# main.net
KiCad netlist of a schematic drawn in EAGLE
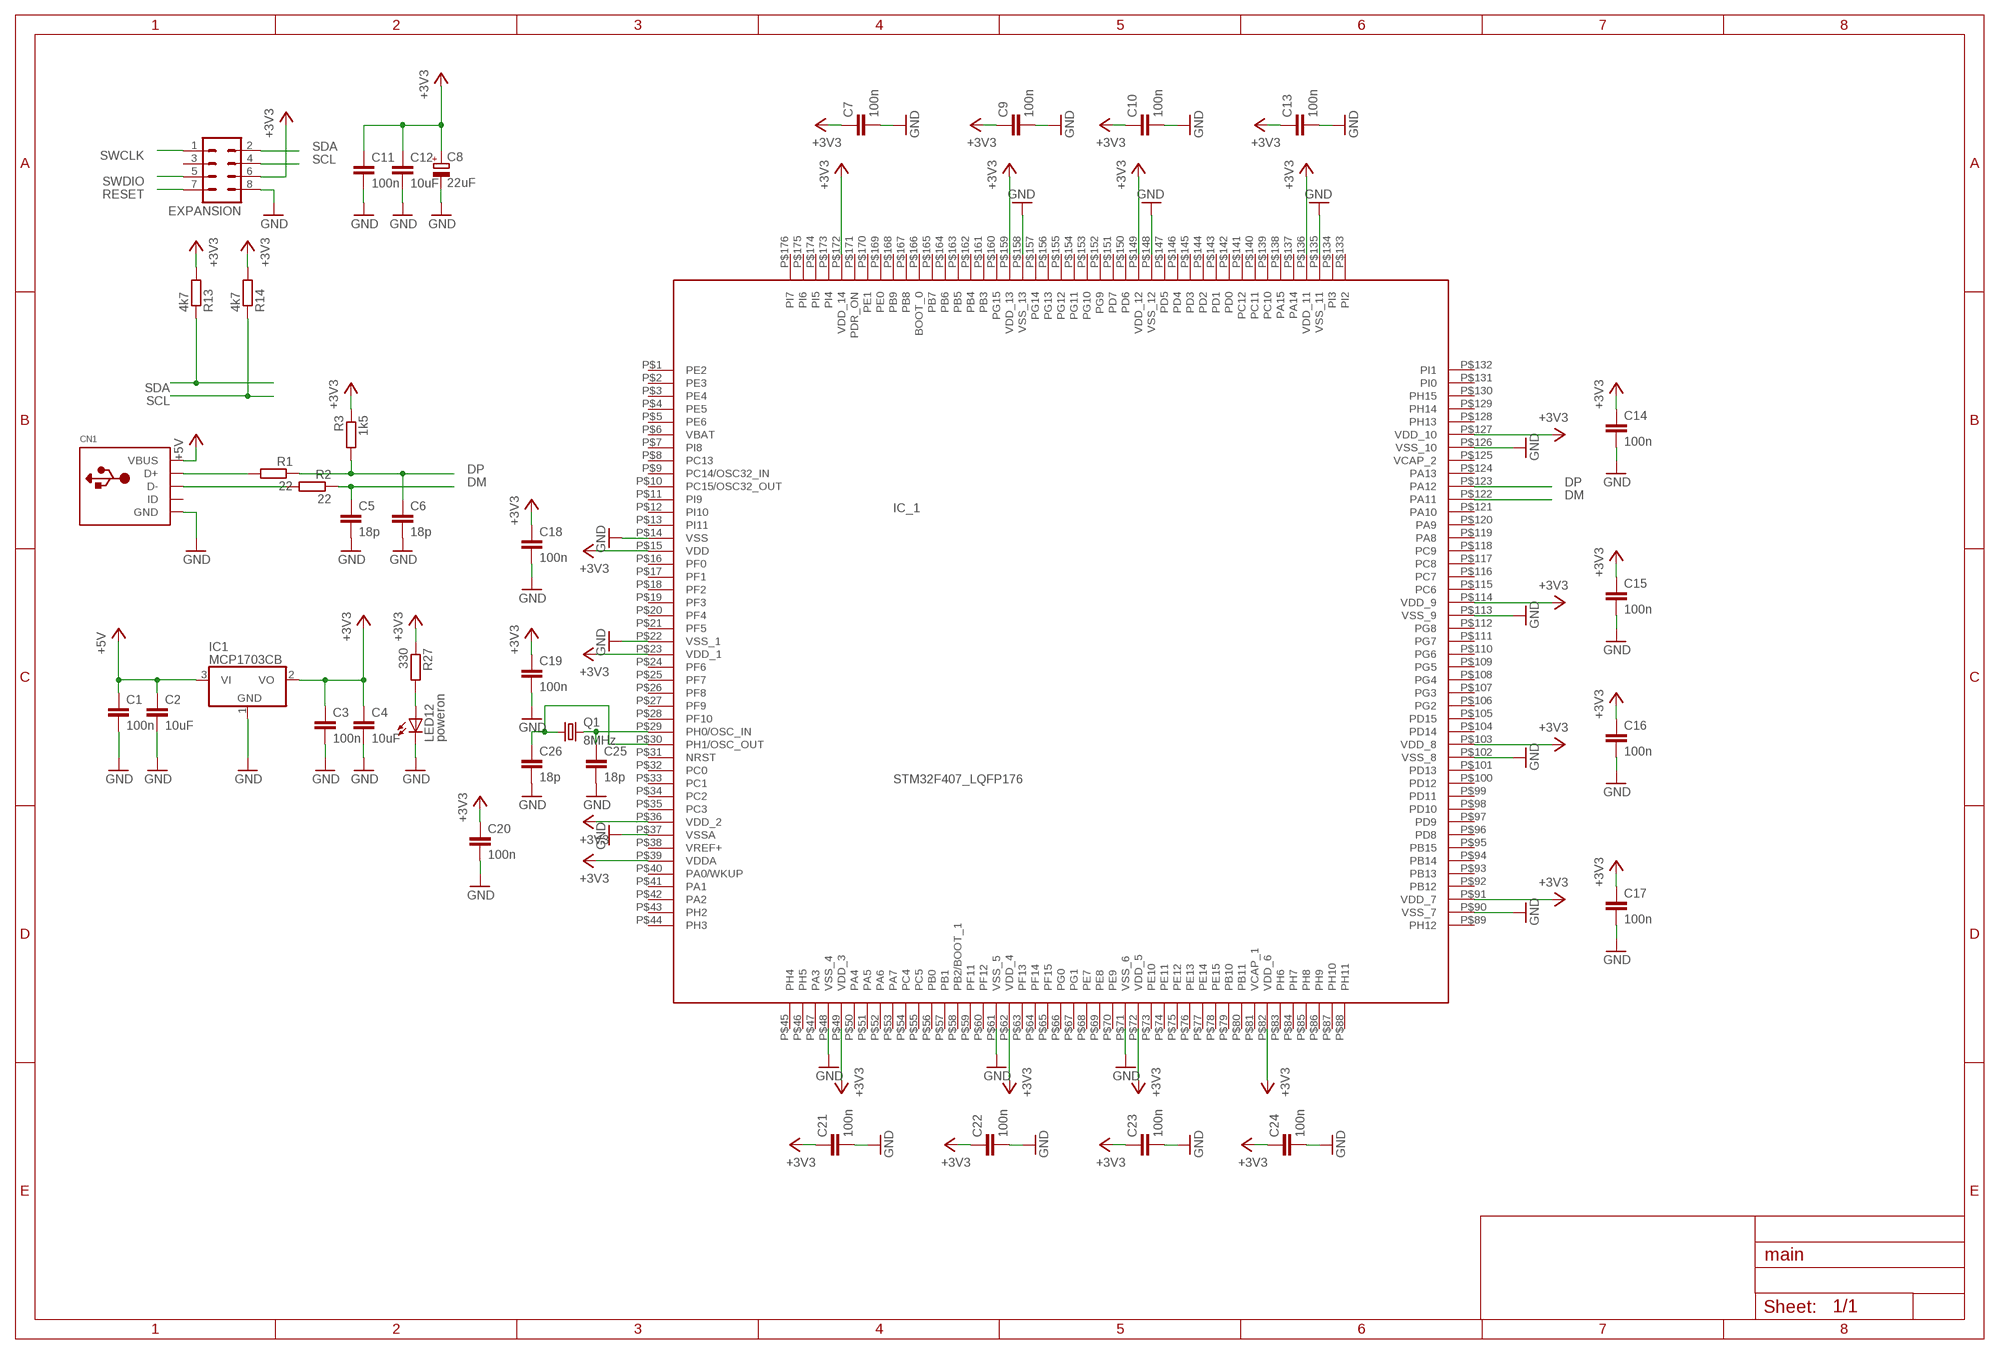
[diagram p0: schematic, sheet 1]

(export (version "E")
  (design (tool "Eeschema 10.0.6"))
  (components
    (comp (ref "C1")
      (value "100n")
      (footprint "eagle-import:C0805")
      (libsource (lib "eagle-import") (part "C-EUC0805"))
    )
    (comp (ref "C2")
      (value "10uF")
      (footprint "eagle-import:C0805")
      (libsource (lib "eagle-import") (part "C-EUC0805"))
    )
    (comp (ref "C3")
      (value "100n")
      (footprint "eagle-import:C0805")
      (libsource (lib "eagle-import") (part "C-EUC0805"))
    )
    (comp (ref "C4")
      (value "10uF")
      (footprint "eagle-import:C0805")
      (libsource (lib "eagle-import") (part "C-EUC0805"))
    )
    (comp (ref "C5")
      (value "18p")
      (footprint "eagle-import:C0805")
      (libsource (lib "eagle-import") (part "C-EUC0805"))
    )
    (comp (ref "C6")
      (value "18p")
      (footprint "eagle-import:C0805")
      (libsource (lib "eagle-import") (part "C-EUC0805"))
    )
    (comp (ref "C7")
      (value "100n")
      (footprint "eagle-import:C0805")
      (libsource (lib "eagle-import") (part "C-EUC0805"))
    )
    (comp (ref "C8")
      (value "22uF")
      (footprint "eagle-import:153CLV-0505")
      (libsource (lib "eagle-import") (part "CPOL-EU153CLV-0505"))
    )
    (comp (ref "C9")
      (value "100n")
      (footprint "eagle-import:C0805")
      (libsource (lib "eagle-import") (part "C-EUC0805"))
    )
    (comp (ref "C10")
      (value "100n")
      (footprint "eagle-import:C0805")
      (libsource (lib "eagle-import") (part "C-EUC0805"))
    )
    (comp (ref "C11")
      (value "100n")
      (footprint "eagle-import:C0805")
      (libsource (lib "eagle-import") (part "C-EUC0805"))
    )
    (comp (ref "C12")
      (value "10uF")
      (footprint "eagle-import:C0805")
      (libsource (lib "eagle-import") (part "C-EUC0805"))
    )
    (comp (ref "C13")
      (value "100n")
      (footprint "eagle-import:C0805")
      (libsource (lib "eagle-import") (part "C-EUC0805"))
    )
    (comp (ref "C14")
      (value "100n")
      (footprint "eagle-import:C0805")
      (libsource (lib "eagle-import") (part "C-EUC0805"))
    )
    (comp (ref "C15")
      (value "100n")
      (footprint "eagle-import:C0805")
      (libsource (lib "eagle-import") (part "C-EUC0805"))
    )
    (comp (ref "C16")
      (value "100n")
      (footprint "eagle-import:C0805")
      (libsource (lib "eagle-import") (part "C-EUC0805"))
    )
    (comp (ref "C17")
      (value "100n")
      (footprint "eagle-import:C0805")
      (libsource (lib "eagle-import") (part "C-EUC0805"))
    )
    (comp (ref "C18")
      (value "100n")
      (footprint "eagle-import:C0805")
      (libsource (lib "eagle-import") (part "C-EUC0805"))
    )
    (comp (ref "C19")
      (value "100n")
      (footprint "eagle-import:C0805")
      (libsource (lib "eagle-import") (part "C-EUC0805"))
    )
    (comp (ref "C20")
      (value "100n")
      (footprint "eagle-import:C0805")
      (libsource (lib "eagle-import") (part "C-EUC0805"))
    )
    (comp (ref "C21")
      (value "100n")
      (footprint "eagle-import:C0805")
      (libsource (lib "eagle-import") (part "C-EUC0805"))
    )
    (comp (ref "C22")
      (value "100n")
      (footprint "eagle-import:C0805")
      (libsource (lib "eagle-import") (part "C-EUC0805"))
    )
    (comp (ref "C23")
      (value "100n")
      (footprint "eagle-import:C0805")
      (libsource (lib "eagle-import") (part "C-EUC0805"))
    )
    (comp (ref "C24")
      (value "100n")
      (footprint "eagle-import:C0805")
      (libsource (lib "eagle-import") (part "C-EUC0805"))
    )
    (comp (ref "C25")
      (value "18p")
      (footprint "eagle-import:C0805")
      (libsource (lib "eagle-import") (part "C-EUC0805"))
    )
    (comp (ref "C26")
      (value "18p")
      (footprint "eagle-import:C0805")
      (libsource (lib "eagle-import") (part "C-EUC0805"))
    )
    (comp (ref "CN1")
      (value "USBMINIB")
      (footprint "eagle-import:USB-MINIB")
      (libsource (lib "eagle-import") (part "USBMINIB"))
    )
    (comp (ref "EXPANSION")
      (value "MA04-2")
      (footprint "eagle-import:MA04-2")
      (libsource (lib "eagle-import") (part "MA04-2"))
    )
    (comp (ref "IC1")
      (value "MCP1703CB")
      (footprint "eagle-import:SOT23")
      (libsource (lib "eagle-import") (part "MCP1703CB"))
    )
    (comp (ref "IC_1")
      (value "STM32F407_LQFP176")
      (footprint "eagle-import:STM32F407_LQFP176")
      (libsource (lib "eagle-import") (part "STM32F407_LQFP176"))
    )
    (comp (ref "LED12")
      (value "poweron")
      (footprint "eagle-import:CHIPLED_1206")
      (libsource (lib "eagle-import") (part "LEDCHIPLED_1206"))
    )
    (comp (ref "Q1")
      (value "8MHz")
      (footprint "eagle-import:CTS406")
      (libsource (lib "eagle-import") (part "CRYSTALCTS406"))
    )
    (comp (ref "R1")
      (value "22")
      (footprint "eagle-import:M0805")
      (libsource (lib "eagle-import") (part "R-EU_M0805"))
    )
    (comp (ref "R2")
      (value "22")
      (footprint "eagle-import:M0805")
      (libsource (lib "eagle-import") (part "R-EU_M0805"))
    )
    (comp (ref "R3")
      (value "1k5")
      (footprint "eagle-import:M0805")
      (libsource (lib "eagle-import") (part "R-EU_M0805"))
    )
    (comp (ref "R13")
      (value "4k7")
      (footprint "eagle-import:M0805")
      (libsource (lib "eagle-import") (part "R-EU_M0805"))
    )
    (comp (ref "R14")
      (value "4k7")
      (footprint "eagle-import:M0805")
      (libsource (lib "eagle-import") (part "R-EU_M0805"))
    )
    (comp (ref "R27")
      (value "330")
      (footprint "eagle-import:M0805")
      (libsource (lib "eagle-import") (part "R-EU_M0805"))
    )
  )
  (nets
    (net (code "1") (name "+3V3") (class "Default")
      (node (ref "C10") (pin "1") (pinfunction "1_1") (pintype "passive"))
      (node (ref "C11") (pin "1") (pinfunction "1_1") (pintype "passive"))
      (node (ref "C12") (pin "1") (pinfunction "1_1") (pintype "passive"))
      (node (ref "C13") (pin "1") (pinfunction "1_1") (pintype "passive"))
      (node (ref "C14") (pin "1") (pinfunction "1_1") (pintype "passive"))
      (node (ref "C15") (pin "1") (pinfunction "1_1") (pintype "passive"))
      (node (ref "C16") (pin "1") (pinfunction "1_1") (pintype "passive"))
      (node (ref "C17") (pin "1") (pinfunction "1_1") (pintype "passive"))
      (node (ref "C18") (pin "1") (pinfunction "1_1") (pintype "passive"))
      (node (ref "C19") (pin "1") (pinfunction "1_1") (pintype "passive"))
      (node (ref "C20") (pin "1") (pinfunction "1_1") (pintype "passive"))
      (node (ref "C21") (pin "1") (pinfunction "1_1") (pintype "passive"))
      (node (ref "C22") (pin "1") (pinfunction "1_1") (pintype "passive"))
      (node (ref "C23") (pin "1") (pinfunction "1_1") (pintype "passive"))
      (node (ref "C24") (pin "1") (pinfunction "1_1") (pintype "passive"))
      (node (ref "C3") (pin "1") (pinfunction "1_1") (pintype "passive"))
      (node (ref "C4") (pin "1") (pinfunction "1_1") (pintype "passive"))
      (node (ref "C7") (pin "1") (pinfunction "1_1") (pintype "passive"))
      (node (ref "C8") (pin "+") (pinfunction "+_+") (pintype "passive"))
      (node (ref "C9") (pin "1") (pinfunction "1_1") (pintype "passive"))
      (node (ref "EXPANSION") (pin "6") (pinfunction "6_6") (pintype "passive"))
      (node (ref "IC1") (pin "2") (pinfunction "VO_2") (pintype "passive"))
      (node (ref "IC_1") (pin "P$103") (pinfunction "VDD_8_P$103") (pintype "power_in"))
      (node (ref "IC_1") (pin "P$114") (pinfunction "VDD_9_P$114") (pintype "power_in"))
      (node (ref "IC_1") (pin "P$127") (pinfunction "VDD_10_P$127") (pintype "power_in"))
      (node (ref "IC_1") (pin "P$136") (pinfunction "VDD_11_P$136") (pintype "power_in"))
      (node (ref "IC_1") (pin "P$149") (pinfunction "VDD_12_P$149") (pintype "power_in"))
      (node (ref "IC_1") (pin "P$15") (pinfunction "VDD_P$15") (pintype "power_in"))
      (node (ref "IC_1") (pin "P$159") (pinfunction "VDD_13_P$159") (pintype "power_in"))
      (node (ref "IC_1") (pin "P$172") (pinfunction "VDD_14_P$172") (pintype "power_in"))
      (node (ref "IC_1") (pin "P$23") (pinfunction "VDD_1_P$23") (pintype "power_in"))
      (node (ref "IC_1") (pin "P$36") (pinfunction "VDD_2_P$36") (pintype "power_in"))
      (node (ref "IC_1") (pin "P$39") (pinfunction "VDDA_P$39") (pintype "power_in"))
      (node (ref "IC_1") (pin "P$49") (pinfunction "VDD_3_P$49") (pintype "power_in"))
      (node (ref "IC_1") (pin "P$62") (pinfunction "VDD_4_P$62") (pintype "power_in"))
      (node (ref "IC_1") (pin "P$72") (pinfunction "VDD_5_P$72") (pintype "power_in"))
      (node (ref "IC_1") (pin "P$82") (pinfunction "VDD_6_P$82") (pintype "power_in"))
      (node (ref "IC_1") (pin "P$91") (pinfunction "VDD_7_P$91") (pintype "power_in"))
      (node (ref "R13") (pin "2") (pinfunction "2_2") (pintype "passive"))
      (node (ref "R14") (pin "2") (pinfunction "2_2") (pintype "passive"))
      (node (ref "R27") (pin "1") (pinfunction "1_1") (pintype "passive"))
      (node (ref "R3") (pin "1") (pinfunction "1_1") (pintype "passive"))
    )
    (net (code "2") (name "+5V") (class "Default")
      (node (ref "C1") (pin "1") (pinfunction "1_1") (pintype "passive"))
      (node (ref "C2") (pin "1") (pinfunction "1_1") (pintype "passive"))
      (node (ref "CN1") (pin "VBUS") (pinfunction "VBUS_VBUS") (pintype "power_in"))
      (node (ref "IC1") (pin "3") (pinfunction "VI_3") (pintype "input"))
    )
    (net (code "3") (name "/DM") (class "Default")
      (node (ref "C5") (pin "1") (pinfunction "1_1") (pintype "passive"))
      (node (ref "IC_1") (pin "P$122") (pinfunction "PA11_P$122") (pintype "bidirectional"))
      (node (ref "R2") (pin "1") (pinfunction "1_1") (pintype "passive"))
    )
    (net (code "4") (name "/DP") (class "Default")
      (node (ref "C6") (pin "1") (pinfunction "1_1") (pintype "passive"))
      (node (ref "IC_1") (pin "P$123") (pinfunction "PA12_P$123") (pintype "bidirectional"))
      (node (ref "R1") (pin "1") (pinfunction "1_1") (pintype "passive"))
      (node (ref "R3") (pin "2") (pinfunction "2_2") (pintype "passive"))
    )
    (net (code "5") (name "/RESET") (class "Default")
      (node (ref "EXPANSION") (pin "7") (pinfunction "7_7") (pintype "passive"))
    )
    (net (code "6") (name "/SCL") (class "Default")
      (node (ref "EXPANSION") (pin "4") (pinfunction "4_4") (pintype "passive"))
      (node (ref "R14") (pin "1") (pinfunction "1_1") (pintype "passive"))
    )
    (net (code "7") (name "/SDA") (class "Default")
      (node (ref "EXPANSION") (pin "2") (pinfunction "2_2") (pintype "passive"))
      (node (ref "R13") (pin "1") (pinfunction "1_1") (pintype "passive"))
    )
    (net (code "8") (name "/SWCLK") (class "Default")
      (node (ref "EXPANSION") (pin "1") (pinfunction "1_1") (pintype "passive"))
    )
    (net (code "9") (name "/SWDIO") (class "Default")
      (node (ref "EXPANSION") (pin "5") (pinfunction "5_5") (pintype "passive"))
    )
    (net (code "10") (name "/VBAT") (class "Default")
      (node (ref "IC_1") (pin "P$6") (pinfunction "VBAT_P$6") (pintype "power_in"))
    )
    (net (code "11") (name "/VCAP_1") (class "Default")
      (node (ref "IC_1") (pin "P$81") (pinfunction "VCAP_1_P$81") (pintype "power_in"))
    )
    (net (code "12") (name "/VCAP_2") (class "Default")
      (node (ref "IC_1") (pin "P$125") (pinfunction "VCAP_2_P$125") (pintype "power_in"))
    )
    (net (code "13") (name "/VREF+") (class "Default")
      (node (ref "IC_1") (pin "P$38") (pinfunction "VREF+_P$38") (pintype "power_in"))
    )
    (net (code "14") (name "GND") (class "Default")
      (node (ref "C1") (pin "2") (pinfunction "2_2") (pintype "passive"))
      (node (ref "C10") (pin "2") (pinfunction "2_2") (pintype "passive"))
      (node (ref "C11") (pin "2") (pinfunction "2_2") (pintype "passive"))
      (node (ref "C12") (pin "2") (pinfunction "2_2") (pintype "passive"))
      (node (ref "C13") (pin "2") (pinfunction "2_2") (pintype "passive"))
      (node (ref "C14") (pin "2") (pinfunction "2_2") (pintype "passive"))
      (node (ref "C15") (pin "2") (pinfunction "2_2") (pintype "passive"))
      (node (ref "C16") (pin "2") (pinfunction "2_2") (pintype "passive"))
      (node (ref "C17") (pin "2") (pinfunction "2_2") (pintype "passive"))
      (node (ref "C18") (pin "2") (pinfunction "2_2") (pintype "passive"))
      (node (ref "C19") (pin "2") (pinfunction "2_2") (pintype "passive"))
      (node (ref "C2") (pin "2") (pinfunction "2_2") (pintype "passive"))
      (node (ref "C20") (pin "2") (pinfunction "2_2") (pintype "passive"))
      (node (ref "C21") (pin "2") (pinfunction "2_2") (pintype "passive"))
      (node (ref "C22") (pin "2") (pinfunction "2_2") (pintype "passive"))
      (node (ref "C23") (pin "2") (pinfunction "2_2") (pintype "passive"))
      (node (ref "C24") (pin "2") (pinfunction "2_2") (pintype "passive"))
      (node (ref "C25") (pin "2") (pinfunction "2_2") (pintype "passive"))
      (node (ref "C26") (pin "2") (pinfunction "2_2") (pintype "passive"))
      (node (ref "C3") (pin "2") (pinfunction "2_2") (pintype "passive"))
      (node (ref "C4") (pin "2") (pinfunction "2_2") (pintype "passive"))
      (node (ref "C5") (pin "2") (pinfunction "2_2") (pintype "passive"))
      (node (ref "C6") (pin "2") (pinfunction "2_2") (pintype "passive"))
      (node (ref "C7") (pin "2") (pinfunction "2_2") (pintype "passive"))
      (node (ref "C8") (pin "-") (pinfunction "-_-") (pintype "passive"))
      (node (ref "C9") (pin "2") (pinfunction "2_2") (pintype "passive"))
      (node (ref "CN1") (pin "GND") (pinfunction "GND_GND") (pintype "power_in"))
      (node (ref "EXPANSION") (pin "8") (pinfunction "8_8") (pintype "passive"))
      (node (ref "IC1") (pin "1") (pinfunction "GND_1") (pintype "passive"))
      (node (ref "IC_1") (pin "P$102") (pinfunction "VSS_8_P$102") (pintype "power_in"))
      (node (ref "IC_1") (pin "P$113") (pinfunction "VSS_9_P$113") (pintype "power_in"))
      (node (ref "IC_1") (pin "P$126") (pinfunction "VSS_10_P$126") (pintype "power_in"))
      (node (ref "IC_1") (pin "P$135") (pinfunction "VSS_11_P$135") (pintype "power_in"))
      (node (ref "IC_1") (pin "P$14") (pinfunction "VSS_P$14") (pintype "power_in"))
      (node (ref "IC_1") (pin "P$148") (pinfunction "VSS_12_P$148") (pintype "power_in"))
      (node (ref "IC_1") (pin "P$158") (pinfunction "VSS_13_P$158") (pintype "power_in"))
      (node (ref "IC_1") (pin "P$22") (pinfunction "VSS_1_P$22") (pintype "power_in"))
      (node (ref "IC_1") (pin "P$37") (pinfunction "VSSA_P$37") (pintype "power_in"))
      (node (ref "IC_1") (pin "P$48") (pinfunction "VSS_4_P$48") (pintype "power_in"))
      (node (ref "IC_1") (pin "P$61") (pinfunction "VSS_5_P$61") (pintype "power_in"))
      (node (ref "IC_1") (pin "P$71") (pinfunction "VSS_6_P$71") (pintype "power_in"))
      (node (ref "IC_1") (pin "P$90") (pinfunction "VSS_7_P$90") (pintype "power_in"))
      (node (ref "LED12") (pin "C") (pinfunction "C_C") (pintype "passive"))
    )
    (net (code "15") (name "Net-(CN1-PadD+)") (class "Default")
      (node (ref "CN1") (pin "D+") (pinfunction "D+_D+") (pintype "bidirectional"))
      (node (ref "R1") (pin "2") (pinfunction "2_2") (pintype "passive"))
    )
    (net (code "16") (name "Net-(CN1-PadD-)") (class "Default")
      (node (ref "CN1") (pin "D-") (pinfunction "D-_D-") (pintype "bidirectional"))
      (node (ref "R2") (pin "2") (pinfunction "2_2") (pintype "passive"))
    )
    (net (code "17") (name "Net-(IC_1-PH0{slash}OSC_IN)") (class "Default")
      (node (ref "C25") (pin "1") (pinfunction "1_1") (pintype "passive"))
      (node (ref "IC_1") (pin "P$29") (pinfunction "PH0/OSC_IN_P$29") (pintype "bidirectional"))
      (node (ref "Q1") (pin "3") (pinfunction "2_3") (pintype "passive"))
    )
    (net (code "18") (name "Net-(IC_1-PH1{slash}OSC_OUT)") (class "Default")
      (node (ref "C26") (pin "1") (pinfunction "1_1") (pintype "passive"))
      (node (ref "IC_1") (pin "P$30") (pinfunction "PH1/OSC_OUT_P$30") (pintype "bidirectional"))
      (node (ref "Q1") (pin "1") (pinfunction "1_1") (pintype "passive"))
    )
    (net (code "19") (name "Net-(LED12-PadA)") (class "Default")
      (node (ref "LED12") (pin "A") (pinfunction "A_A") (pintype "passive"))
      (node (ref "R27") (pin "2") (pinfunction "2_2") (pintype "passive"))
    )
    (net (code "20") (name "unconnected-(CN1-PadID)") (class "Default")
      (node (ref "CN1") (pin "ID") (pinfunction "ID_ID") (pintype "bidirectional"))
    )
    (net (code "21") (name "unconnected-(EXPANSION-Pad3)") (class "Default")
      (node (ref "EXPANSION") (pin "3") (pinfunction "3_3") (pintype "passive"))
    )
    (net (code "22") (name "unconnected-(IC_1-BOOT_0-PadP$166)") (class "Default")
      (node (ref "IC_1") (pin "P$166") (pinfunction "BOOT_0_P$166") (pintype "bidirectional"))
    )
    (net (code "23") (name "unconnected-(IC_1-NRST-PadP$31)") (class "Default")
      (node (ref "IC_1") (pin "P$31") (pinfunction "NRST_P$31") (pintype "bidirectional"))
    )
    (net (code "24") (name "unconnected-(IC_1-PA0{slash}WKUP-PadP$40)") (class "Default")
      (node (ref "IC_1") (pin "P$40") (pinfunction "PA0/WKUP_P$40") (pintype "bidirectional"))
    )
    (net (code "25") (name "unconnected-(IC_1-PA1-PadP$41)") (class "Default")
      (node (ref "IC_1") (pin "P$41") (pinfunction "PA1_P$41") (pintype "bidirectional"))
    )
    (net (code "26") (name "unconnected-(IC_1-PA2-PadP$42)") (class "Default")
      (node (ref "IC_1") (pin "P$42") (pinfunction "PA2_P$42") (pintype "bidirectional"))
    )
    (net (code "27") (name "unconnected-(IC_1-PA3-PadP$47)") (class "Default")
      (node (ref "IC_1") (pin "P$47") (pinfunction "PA3_P$47") (pintype "bidirectional"))
    )
    (net (code "28") (name "unconnected-(IC_1-PA4-PadP$50)") (class "Default")
      (node (ref "IC_1") (pin "P$50") (pinfunction "PA4_P$50") (pintype "bidirectional"))
    )
    (net (code "29") (name "unconnected-(IC_1-PA5-PadP$51)") (class "Default")
      (node (ref "IC_1") (pin "P$51") (pinfunction "PA5_P$51") (pintype "bidirectional"))
    )
    (net (code "30") (name "unconnected-(IC_1-PA6-PadP$52)") (class "Default")
      (node (ref "IC_1") (pin "P$52") (pinfunction "PA6_P$52") (pintype "bidirectional"))
    )
    (net (code "31") (name "unconnected-(IC_1-PA7-PadP$53)") (class "Default")
      (node (ref "IC_1") (pin "P$53") (pinfunction "PA7_P$53") (pintype "bidirectional"))
    )
    (net (code "32") (name "unconnected-(IC_1-PA8-PadP$119)") (class "Default")
      (node (ref "IC_1") (pin "P$119") (pinfunction "PA8_P$119") (pintype "bidirectional"))
    )
    (net (code "33") (name "unconnected-(IC_1-PA9-PadP$120)") (class "Default")
      (node (ref "IC_1") (pin "P$120") (pinfunction "PA9_P$120") (pintype "bidirectional"))
    )
    (net (code "34") (name "unconnected-(IC_1-PA10-PadP$121)") (class "Default")
      (node (ref "IC_1") (pin "P$121") (pinfunction "PA10_P$121") (pintype "bidirectional"))
    )
    (net (code "35") (name "unconnected-(IC_1-PA13-PadP$124)") (class "Default")
      (node (ref "IC_1") (pin "P$124") (pinfunction "PA13_P$124") (pintype "bidirectional"))
    )
    (net (code "36") (name "unconnected-(IC_1-PA14-PadP$137)") (class "Default")
      (node (ref "IC_1") (pin "P$137") (pinfunction "PA14_P$137") (pintype "bidirectional"))
    )
    (net (code "37") (name "unconnected-(IC_1-PA15-PadP$138)") (class "Default")
      (node (ref "IC_1") (pin "P$138") (pinfunction "PA15_P$138") (pintype "bidirectional"))
    )
    (net (code "38") (name "unconnected-(IC_1-PB0-PadP$56)") (class "Default")
      (node (ref "IC_1") (pin "P$56") (pinfunction "PB0_P$56") (pintype "bidirectional"))
    )
    (net (code "39") (name "unconnected-(IC_1-PB1-PadP$57)") (class "Default")
      (node (ref "IC_1") (pin "P$57") (pinfunction "PB1_P$57") (pintype "bidirectional"))
    )
    (net (code "40") (name "unconnected-(IC_1-PB2{slash}BOOT_1-PadP$58)") (class "Default")
      (node (ref "IC_1") (pin "P$58") (pinfunction "PB2/BOOT_1_P$58") (pintype "bidirectional"))
    )
    (net (code "41") (name "unconnected-(IC_1-PB3-PadP$161)") (class "Default")
      (node (ref "IC_1") (pin "P$161") (pinfunction "PB3_P$161") (pintype "bidirectional"))
    )
    (net (code "42") (name "unconnected-(IC_1-PB4-PadP$162)") (class "Default")
      (node (ref "IC_1") (pin "P$162") (pinfunction "PB4_P$162") (pintype "bidirectional"))
    )
    (net (code "43") (name "unconnected-(IC_1-PB5-PadP$163)") (class "Default")
      (node (ref "IC_1") (pin "P$163") (pinfunction "PB5_P$163") (pintype "bidirectional"))
    )
    (net (code "44") (name "unconnected-(IC_1-PB6-PadP$164)") (class "Default")
      (node (ref "IC_1") (pin "P$164") (pinfunction "PB6_P$164") (pintype "bidirectional"))
    )
    (net (code "45") (name "unconnected-(IC_1-PB7-PadP$165)") (class "Default")
      (node (ref "IC_1") (pin "P$165") (pinfunction "PB7_P$165") (pintype "bidirectional"))
    )
    (net (code "46") (name "unconnected-(IC_1-PB8-PadP$167)") (class "Default")
      (node (ref "IC_1") (pin "P$167") (pinfunction "PB8_P$167") (pintype "bidirectional"))
    )
    (net (code "47") (name "unconnected-(IC_1-PB9-PadP$168)") (class "Default")
      (node (ref "IC_1") (pin "P$168") (pinfunction "PB9_P$168") (pintype "bidirectional"))
    )
    (net (code "48") (name "unconnected-(IC_1-PB10-PadP$79)") (class "Default")
      (node (ref "IC_1") (pin "P$79") (pinfunction "PB10_P$79") (pintype "bidirectional"))
    )
    (net (code "49") (name "unconnected-(IC_1-PB11-PadP$80)") (class "Default")
      (node (ref "IC_1") (pin "P$80") (pinfunction "PB11_P$80") (pintype "bidirectional"))
    )
    (net (code "50") (name "unconnected-(IC_1-PB12-PadP$92)") (class "Default")
      (node (ref "IC_1") (pin "P$92") (pinfunction "PB12_P$92") (pintype "bidirectional"))
    )
    (net (code "51") (name "unconnected-(IC_1-PB13-PadP$93)") (class "Default")
      (node (ref "IC_1") (pin "P$93") (pinfunction "PB13_P$93") (pintype "bidirectional"))
    )
    (net (code "52") (name "unconnected-(IC_1-PB14-PadP$94)") (class "Default")
      (node (ref "IC_1") (pin "P$94") (pinfunction "PB14_P$94") (pintype "bidirectional"))
    )
    (net (code "53") (name "unconnected-(IC_1-PB15-PadP$95)") (class "Default")
      (node (ref "IC_1") (pin "P$95") (pinfunction "PB15_P$95") (pintype "bidirectional"))
    )
    (net (code "54") (name "unconnected-(IC_1-PC0-PadP$32)") (class "Default")
      (node (ref "IC_1") (pin "P$32") (pinfunction "PC0_P$32") (pintype "bidirectional"))
    )
    (net (code "55") (name "unconnected-(IC_1-PC1-PadP$33)") (class "Default")
      (node (ref "IC_1") (pin "P$33") (pinfunction "PC1_P$33") (pintype "bidirectional"))
    )
    (net (code "56") (name "unconnected-(IC_1-PC2-PadP$34)") (class "Default")
      (node (ref "IC_1") (pin "P$34") (pinfunction "PC2_P$34") (pintype "bidirectional"))
    )
    (net (code "57") (name "unconnected-(IC_1-PC3-PadP$35)") (class "Default")
      (node (ref "IC_1") (pin "P$35") (pinfunction "PC3_P$35") (pintype "bidirectional"))
    )
    (net (code "58") (name "unconnected-(IC_1-PC4-PadP$54)") (class "Default")
      (node (ref "IC_1") (pin "P$54") (pinfunction "PC4_P$54") (pintype "bidirectional"))
    )
    (net (code "59") (name "unconnected-(IC_1-PC5-PadP$55)") (class "Default")
      (node (ref "IC_1") (pin "P$55") (pinfunction "PC5_P$55") (pintype "bidirectional"))
    )
    (net (code "60") (name "unconnected-(IC_1-PC6-PadP$115)") (class "Default")
      (node (ref "IC_1") (pin "P$115") (pinfunction "PC6_P$115") (pintype "bidirectional"))
    )
    (net (code "61") (name "unconnected-(IC_1-PC7-PadP$116)") (class "Default")
      (node (ref "IC_1") (pin "P$116") (pinfunction "PC7_P$116") (pintype "bidirectional"))
    )
    (net (code "62") (name "unconnected-(IC_1-PC8-PadP$117)") (class "Default")
      (node (ref "IC_1") (pin "P$117") (pinfunction "PC8_P$117") (pintype "bidirectional"))
    )
    (net (code "63") (name "unconnected-(IC_1-PC9-PadP$118)") (class "Default")
      (node (ref "IC_1") (pin "P$118") (pinfunction "PC9_P$118") (pintype "bidirectional"))
    )
    (net (code "64") (name "unconnected-(IC_1-PC10-PadP$139)") (class "Default")
      (node (ref "IC_1") (pin "P$139") (pinfunction "PC10_P$139") (pintype "bidirectional"))
    )
    (net (code "65") (name "unconnected-(IC_1-PC11-PadP$140)") (class "Default")
      (node (ref "IC_1") (pin "P$140") (pinfunction "PC11_P$140") (pintype "bidirectional"))
    )
    (net (code "66") (name "unconnected-(IC_1-PC12-PadP$141)") (class "Default")
      (node (ref "IC_1") (pin "P$141") (pinfunction "PC12_P$141") (pintype "bidirectional"))
    )
    (net (code "67") (name "unconnected-(IC_1-PC13-PadP$8)") (class "Default")
      (node (ref "IC_1") (pin "P$8") (pinfunction "PC13_P$8") (pintype "bidirectional"))
    )
    (net (code "68") (name "unconnected-(IC_1-PC14{slash}OSC32_IN-PadP$9)") (class "Default")
      (node (ref "IC_1") (pin "P$9") (pinfunction "PC14/OSC32_IN_P$9") (pintype "bidirectional"))
    )
    (net (code "69") (name "unconnected-(IC_1-PC15{slash}OSC32_OUT-PadP$10)") (class "Default")
      (node (ref "IC_1") (pin "P$10") (pinfunction "PC15/OSC32_OUT_P$10") (pintype "bidirectional"))
    )
    (net (code "70") (name "unconnected-(IC_1-PD0-PadP$142)") (class "Default")
      (node (ref "IC_1") (pin "P$142") (pinfunction "PD0_P$142") (pintype "bidirectional"))
    )
    (net (code "71") (name "unconnected-(IC_1-PD1-PadP$143)") (class "Default")
      (node (ref "IC_1") (pin "P$143") (pinfunction "PD1_P$143") (pintype "bidirectional"))
    )
    (net (code "72") (name "unconnected-(IC_1-PD2-PadP$144)") (class "Default")
      (node (ref "IC_1") (pin "P$144") (pinfunction "PD2_P$144") (pintype "bidirectional"))
    )
    (net (code "73") (name "unconnected-(IC_1-PD3-PadP$145)") (class "Default")
      (node (ref "IC_1") (pin "P$145") (pinfunction "PD3_P$145") (pintype "bidirectional"))
    )
    (net (code "74") (name "unconnected-(IC_1-PD4-PadP$146)") (class "Default")
      (node (ref "IC_1") (pin "P$146") (pinfunction "PD4_P$146") (pintype "bidirectional"))
    )
    (net (code "75") (name "unconnected-(IC_1-PD5-PadP$147)") (class "Default")
      (node (ref "IC_1") (pin "P$147") (pinfunction "PD5_P$147") (pintype "bidirectional"))
    )
    (net (code "76") (name "unconnected-(IC_1-PD6-PadP$150)") (class "Default")
      (node (ref "IC_1") (pin "P$150") (pinfunction "PD6_P$150") (pintype "bidirectional"))
    )
    (net (code "77") (name "unconnected-(IC_1-PD7-PadP$151)") (class "Default")
      (node (ref "IC_1") (pin "P$151") (pinfunction "PD7_P$151") (pintype "bidirectional"))
    )
    (net (code "78") (name "unconnected-(IC_1-PD8-PadP$96)") (class "Default")
      (node (ref "IC_1") (pin "P$96") (pinfunction "PD8_P$96") (pintype "bidirectional"))
    )
    (net (code "79") (name "unconnected-(IC_1-PD9-PadP$97)") (class "Default")
      (node (ref "IC_1") (pin "P$97") (pinfunction "PD9_P$97") (pintype "bidirectional"))
    )
    (net (code "80") (name "unconnected-(IC_1-PD10-PadP$98)") (class "Default")
      (node (ref "IC_1") (pin "P$98") (pinfunction "PD10_P$98") (pintype "bidirectional"))
    )
    (net (code "81") (name "unconnected-(IC_1-PD11-PadP$99)") (class "Default")
      (node (ref "IC_1") (pin "P$99") (pinfunction "PD11_P$99") (pintype "bidirectional"))
    )
    (net (code "82") (name "unconnected-(IC_1-PD12-PadP$100)") (class "Default")
      (node (ref "IC_1") (pin "P$100") (pinfunction "PD12_P$100") (pintype "bidirectional"))
    )
    (net (code "83") (name "unconnected-(IC_1-PD13-PadP$101)") (class "Default")
      (node (ref "IC_1") (pin "P$101") (pinfunction "PD13_P$101") (pintype "bidirectional"))
    )
    (net (code "84") (name "unconnected-(IC_1-PD14-PadP$104)") (class "Default")
      (node (ref "IC_1") (pin "P$104") (pinfunction "PD14_P$104") (pintype "bidirectional"))
    )
    (net (code "85") (name "unconnected-(IC_1-PD15-PadP$105)") (class "Default")
      (node (ref "IC_1") (pin "P$105") (pinfunction "PD15_P$105") (pintype "bidirectional"))
    )
    (net (code "86") (name "unconnected-(IC_1-PDR_ON-PadP$171)") (class "Default")
      (node (ref "IC_1") (pin "P$171") (pinfunction "PDR_ON_P$171") (pintype "bidirectional"))
    )
    (net (code "87") (name "unconnected-(IC_1-PE0-PadP$169)") (class "Default")
      (node (ref "IC_1") (pin "P$169") (pinfunction "PE0_P$169") (pintype "bidirectional"))
    )
    (net (code "88") (name "unconnected-(IC_1-PE1-PadP$170)") (class "Default")
      (node (ref "IC_1") (pin "P$170") (pinfunction "PE1_P$170") (pintype "bidirectional"))
    )
    (net (code "89") (name "unconnected-(IC_1-PE2-PadP$1)") (class "Default")
      (node (ref "IC_1") (pin "P$1") (pinfunction "PE2_P$1") (pintype "bidirectional"))
    )
    (net (code "90") (name "unconnected-(IC_1-PE3-PadP$2)") (class "Default")
      (node (ref "IC_1") (pin "P$2") (pinfunction "PE3_P$2") (pintype "bidirectional"))
    )
    (net (code "91") (name "unconnected-(IC_1-PE4-PadP$3)") (class "Default")
      (node (ref "IC_1") (pin "P$3") (pinfunction "PE4_P$3") (pintype "bidirectional"))
    )
    (net (code "92") (name "unconnected-(IC_1-PE5-PadP$4)") (class "Default")
      (node (ref "IC_1") (pin "P$4") (pinfunction "PE5_P$4") (pintype "bidirectional"))
    )
    (net (code "93") (name "unconnected-(IC_1-PE6-PadP$5)") (class "Default")
      (node (ref "IC_1") (pin "P$5") (pinfunction "PE6_P$5") (pintype "bidirectional"))
    )
    (net (code "94") (name "unconnected-(IC_1-PE7-PadP$68)") (class "Default")
      (node (ref "IC_1") (pin "P$68") (pinfunction "PE7_P$68") (pintype "bidirectional"))
    )
    (net (code "95") (name "unconnected-(IC_1-PE8-PadP$69)") (class "Default")
      (node (ref "IC_1") (pin "P$69") (pinfunction "PE8_P$69") (pintype "bidirectional"))
    )
    (net (code "96") (name "unconnected-(IC_1-PE9-PadP$70)") (class "Default")
      (node (ref "IC_1") (pin "P$70") (pinfunction "PE9_P$70") (pintype "bidirectional"))
    )
    (net (code "97") (name "unconnected-(IC_1-PE10-PadP$73)") (class "Default")
      (node (ref "IC_1") (pin "P$73") (pinfunction "PE10_P$73") (pintype "bidirectional"))
    )
    (net (code "98") (name "unconnected-(IC_1-PE11-PadP$74)") (class "Default")
      (node (ref "IC_1") (pin "P$74") (pinfunction "PE11_P$74") (pintype "bidirectional"))
    )
    (net (code "99") (name "unconnected-(IC_1-PE12-PadP$75)") (class "Default")
      (node (ref "IC_1") (pin "P$75") (pinfunction "PE12_P$75") (pintype "bidirectional"))
    )
    (net (code "100") (name "unconnected-(IC_1-PE13-PadP$76)") (class "Default")
      (node (ref "IC_1") (pin "P$76") (pinfunction "PE13_P$76") (pintype "bidirectional"))
    )
    (net (code "101") (name "unconnected-(IC_1-PE14-PadP$77)") (class "Default")
      (node (ref "IC_1") (pin "P$77") (pinfunction "PE14_P$77") (pintype "bidirectional"))
    )
    (net (code "102") (name "unconnected-(IC_1-PE15-PadP$78)") (class "Default")
      (node (ref "IC_1") (pin "P$78") (pinfunction "PE15_P$78") (pintype "bidirectional"))
    )
    (net (code "103") (name "unconnected-(IC_1-PF0-PadP$16)") (class "Default")
      (node (ref "IC_1") (pin "P$16") (pinfunction "PF0_P$16") (pintype "bidirectional"))
    )
    (net (code "104") (name "unconnected-(IC_1-PF1-PadP$17)") (class "Default")
      (node (ref "IC_1") (pin "P$17") (pinfunction "PF1_P$17") (pintype "bidirectional"))
    )
    (net (code "105") (name "unconnected-(IC_1-PF2-PadP$18)") (class "Default")
      (node (ref "IC_1") (pin "P$18") (pinfunction "PF2_P$18") (pintype "bidirectional"))
    )
    (net (code "106") (name "unconnected-(IC_1-PF3-PadP$19)") (class "Default")
      (node (ref "IC_1") (pin "P$19") (pinfunction "PF3_P$19") (pintype "bidirectional"))
    )
    (net (code "107") (name "unconnected-(IC_1-PF4-PadP$20)") (class "Default")
      (node (ref "IC_1") (pin "P$20") (pinfunction "PF4_P$20") (pintype "bidirectional"))
    )
    (net (code "108") (name "unconnected-(IC_1-PF5-PadP$21)") (class "Default")
      (node (ref "IC_1") (pin "P$21") (pinfunction "PF5_P$21") (pintype "bidirectional"))
    )
    (net (code "109") (name "unconnected-(IC_1-PF6-PadP$24)") (class "Default")
      (node (ref "IC_1") (pin "P$24") (pinfunction "PF6_P$24") (pintype "bidirectional"))
    )
    (net (code "110") (name "unconnected-(IC_1-PF7-PadP$25)") (class "Default")
      (node (ref "IC_1") (pin "P$25") (pinfunction "PF7_P$25") (pintype "bidirectional"))
    )
    (net (code "111") (name "unconnected-(IC_1-PF8-PadP$26)") (class "Default")
      (node (ref "IC_1") (pin "P$26") (pinfunction "PF8_P$26") (pintype "bidirectional"))
    )
    (net (code "112") (name "unconnected-(IC_1-PF9-PadP$27)") (class "Default")
      (node (ref "IC_1") (pin "P$27") (pinfunction "PF9_P$27") (pintype "bidirectional"))
    )
    (net (code "113") (name "unconnected-(IC_1-PF10-PadP$28)") (class "Default")
      (node (ref "IC_1") (pin "P$28") (pinfunction "PF10_P$28") (pintype "bidirectional"))
    )
    (net (code "114") (name "unconnected-(IC_1-PF11-PadP$59)") (class "Default")
      (node (ref "IC_1") (pin "P$59") (pinfunction "PF11_P$59") (pintype "bidirectional"))
    )
    (net (code "115") (name "unconnected-(IC_1-PF12-PadP$60)") (class "Default")
      (node (ref "IC_1") (pin "P$60") (pinfunction "PF12_P$60") (pintype "bidirectional"))
    )
    (net (code "116") (name "unconnected-(IC_1-PF13-PadP$63)") (class "Default")
      (node (ref "IC_1") (pin "P$63") (pinfunction "PF13_P$63") (pintype "bidirectional"))
    )
    (net (code "117") (name "unconnected-(IC_1-PF14-PadP$64)") (class "Default")
      (node (ref "IC_1") (pin "P$64") (pinfunction "PF14_P$64") (pintype "bidirectional"))
    )
    (net (code "118") (name "unconnected-(IC_1-PF15-PadP$65)") (class "Default")
      (node (ref "IC_1") (pin "P$65") (pinfunction "PF15_P$65") (pintype "bidirectional"))
    )
    (net (code "119") (name "unconnected-(IC_1-PG0-PadP$66)") (class "Default")
      (node (ref "IC_1") (pin "P$66") (pinfunction "PG0_P$66") (pintype "bidirectional"))
    )
    (net (code "120") (name "unconnected-(IC_1-PG1-PadP$67)") (class "Default")
      (node (ref "IC_1") (pin "P$67") (pinfunction "PG1_P$67") (pintype "bidirectional"))
    )
    (net (code "121") (name "unconnected-(IC_1-PG2-PadP$106)") (class "Default")
      (node (ref "IC_1") (pin "P$106") (pinfunction "PG2_P$106") (pintype "bidirectional"))
    )
    (net (code "122") (name "unconnected-(IC_1-PG3-PadP$107)") (class "Default")
      (node (ref "IC_1") (pin "P$107") (pinfunction "PG3_P$107") (pintype "bidirectional"))
    )
    (net (code "123") (name "unconnected-(IC_1-PG4-PadP$108)") (class "Default")
      (node (ref "IC_1") (pin "P$108") (pinfunction "PG4_P$108") (pintype "bidirectional"))
    )
    (net (code "124") (name "unconnected-(IC_1-PG5-PadP$109)") (class "Default")
      (node (ref "IC_1") (pin "P$109") (pinfunction "PG5_P$109") (pintype "bidirectional"))
    )
    (net (code "125") (name "unconnected-(IC_1-PG6-PadP$110)") (class "Default")
      (node (ref "IC_1") (pin "P$110") (pinfunction "PG6_P$110") (pintype "bidirectional"))
    )
    (net (code "126") (name "unconnected-(IC_1-PG7-PadP$111)") (class "Default")
      (node (ref "IC_1") (pin "P$111") (pinfunction "PG7_P$111") (pintype "bidirectional"))
    )
    (net (code "127") (name "unconnected-(IC_1-PG8-PadP$112)") (class "Default")
      (node (ref "IC_1") (pin "P$112") (pinfunction "PG8_P$112") (pintype "bidirectional"))
    )
    (net (code "128") (name "unconnected-(IC_1-PG9-PadP$152)") (class "Default")
      (node (ref "IC_1") (pin "P$152") (pinfunction "PG9_P$152") (pintype "bidirectional"))
    )
    (net (code "129") (name "unconnected-(IC_1-PG10-PadP$153)") (class "Default")
      (node (ref "IC_1") (pin "P$153") (pinfunction "PG10_P$153") (pintype "bidirectional"))
    )
    (net (code "130") (name "unconnected-(IC_1-PG11-PadP$154)") (class "Default")
      (node (ref "IC_1") (pin "P$154") (pinfunction "PG11_P$154") (pintype "bidirectional"))
    )
    (net (code "131") (name "unconnected-(IC_1-PG12-PadP$155)") (class "Default")
      (node (ref "IC_1") (pin "P$155") (pinfunction "PG12_P$155") (pintype "bidirectional"))
    )
    (net (code "132") (name "unconnected-(IC_1-PG13-PadP$156)") (class "Default")
      (node (ref "IC_1") (pin "P$156") (pinfunction "PG13_P$156") (pintype "bidirectional"))
    )
    (net (code "133") (name "unconnected-(IC_1-PG14-PadP$157)") (class "Default")
      (node (ref "IC_1") (pin "P$157") (pinfunction "PG14_P$157") (pintype "bidirectional"))
    )
    (net (code "134") (name "unconnected-(IC_1-PG15-PadP$160)") (class "Default")
      (node (ref "IC_1") (pin "P$160") (pinfunction "PG15_P$160") (pintype "bidirectional"))
    )
    (net (code "135") (name "unconnected-(IC_1-PH2-PadP$43)") (class "Default")
      (node (ref "IC_1") (pin "P$43") (pinfunction "PH2_P$43") (pintype "bidirectional"))
    )
    (net (code "136") (name "unconnected-(IC_1-PH3-PadP$44)") (class "Default")
      (node (ref "IC_1") (pin "P$44") (pinfunction "PH3_P$44") (pintype "bidirectional"))
    )
    (net (code "137") (name "unconnected-(IC_1-PH4-PadP$45)") (class "Default")
      (node (ref "IC_1") (pin "P$45") (pinfunction "PH4_P$45") (pintype "bidirectional"))
    )
    (net (code "138") (name "unconnected-(IC_1-PH5-PadP$46)") (class "Default")
      (node (ref "IC_1") (pin "P$46") (pinfunction "PH5_P$46") (pintype "bidirectional"))
    )
    (net (code "139") (name "unconnected-(IC_1-PH6-PadP$83)") (class "Default")
      (node (ref "IC_1") (pin "P$83") (pinfunction "PH6_P$83") (pintype "bidirectional"))
    )
    (net (code "140") (name "unconnected-(IC_1-PH7-PadP$84)") (class "Default")
      (node (ref "IC_1") (pin "P$84") (pinfunction "PH7_P$84") (pintype "bidirectional"))
    )
    (net (code "141") (name "unconnected-(IC_1-PH8-PadP$85)") (class "Default")
      (node (ref "IC_1") (pin "P$85") (pinfunction "PH8_P$85") (pintype "bidirectional"))
    )
    (net (code "142") (name "unconnected-(IC_1-PH9-PadP$86)") (class "Default")
      (node (ref "IC_1") (pin "P$86") (pinfunction "PH9_P$86") (pintype "bidirectional"))
    )
    (net (code "143") (name "unconnected-(IC_1-PH10-PadP$87)") (class "Default")
      (node (ref "IC_1") (pin "P$87") (pinfunction "PH10_P$87") (pintype "bidirectional"))
    )
    (net (code "144") (name "unconnected-(IC_1-PH11-PadP$88)") (class "Default")
      (node (ref "IC_1") (pin "P$88") (pinfunction "PH11_P$88") (pintype "bidirectional"))
    )
    (net (code "145") (name "unconnected-(IC_1-PH12-PadP$89)") (class "Default")
      (node (ref "IC_1") (pin "P$89") (pinfunction "PH12_P$89") (pintype "bidirectional"))
    )
    (net (code "146") (name "unconnected-(IC_1-PH13-PadP$128)") (class "Default")
      (node (ref "IC_1") (pin "P$128") (pinfunction "PH13_P$128") (pintype "bidirectional"))
    )
    (net (code "147") (name "unconnected-(IC_1-PH14-PadP$129)") (class "Default")
      (node (ref "IC_1") (pin "P$129") (pinfunction "PH14_P$129") (pintype "bidirectional"))
    )
    (net (code "148") (name "unconnected-(IC_1-PH15-PadP$130)") (class "Default")
      (node (ref "IC_1") (pin "P$130") (pinfunction "PH15_P$130") (pintype "bidirectional"))
    )
    (net (code "149") (name "unconnected-(IC_1-PI0-PadP$131)") (class "Default")
      (node (ref "IC_1") (pin "P$131") (pinfunction "PI0_P$131") (pintype "bidirectional"))
    )
    (net (code "150") (name "unconnected-(IC_1-PI1-PadP$132)") (class "Default")
      (node (ref "IC_1") (pin "P$132") (pinfunction "PI1_P$132") (pintype "bidirectional"))
    )
    (net (code "151") (name "unconnected-(IC_1-PI2-PadP$133)") (class "Default")
      (node (ref "IC_1") (pin "P$133") (pinfunction "PI2_P$133") (pintype "bidirectional"))
    )
    (net (code "152") (name "unconnected-(IC_1-PI3-PadP$134)") (class "Default")
      (node (ref "IC_1") (pin "P$134") (pinfunction "PI3_P$134") (pintype "bidirectional"))
    )
    (net (code "153") (name "unconnected-(IC_1-PI4-PadP$173)") (class "Default")
      (node (ref "IC_1") (pin "P$173") (pinfunction "PI4_P$173") (pintype "bidirectional"))
    )
    (net (code "154") (name "unconnected-(IC_1-PI5-PadP$174)") (class "Default")
      (node (ref "IC_1") (pin "P$174") (pinfunction "PI5_P$174") (pintype "bidirectional"))
    )
    (net (code "155") (name "unconnected-(IC_1-PI6-PadP$175)") (class "Default")
      (node (ref "IC_1") (pin "P$175") (pinfunction "PI6_P$175") (pintype "bidirectional"))
    )
    (net (code "156") (name "unconnected-(IC_1-PI7-PadP$176)") (class "Default")
      (node (ref "IC_1") (pin "P$176") (pinfunction "PI7_P$176") (pintype "bidirectional"))
    )
    (net (code "157") (name "unconnected-(IC_1-PI8-PadP$7)") (class "Default")
      (node (ref "IC_1") (pin "P$7") (pinfunction "PI8_P$7") (pintype "bidirectional"))
    )
    (net (code "158") (name "unconnected-(IC_1-PI9-PadP$11)") (class "Default")
      (node (ref "IC_1") (pin "P$11") (pinfunction "PI9_P$11") (pintype "bidirectional"))
    )
    (net (code "159") (name "unconnected-(IC_1-PI10-PadP$12)") (class "Default")
      (node (ref "IC_1") (pin "P$12") (pinfunction "PI10_P$12") (pintype "bidirectional"))
    )
    (net (code "160") (name "unconnected-(IC_1-PI11-PadP$13)") (class "Default")
      (node (ref "IC_1") (pin "P$13") (pinfunction "PI11_P$13") (pintype "bidirectional"))
    )
  )
)
